# STM32L496RG_Breakout.net
KiCad netlist of a schematic drawn in Altium Designer
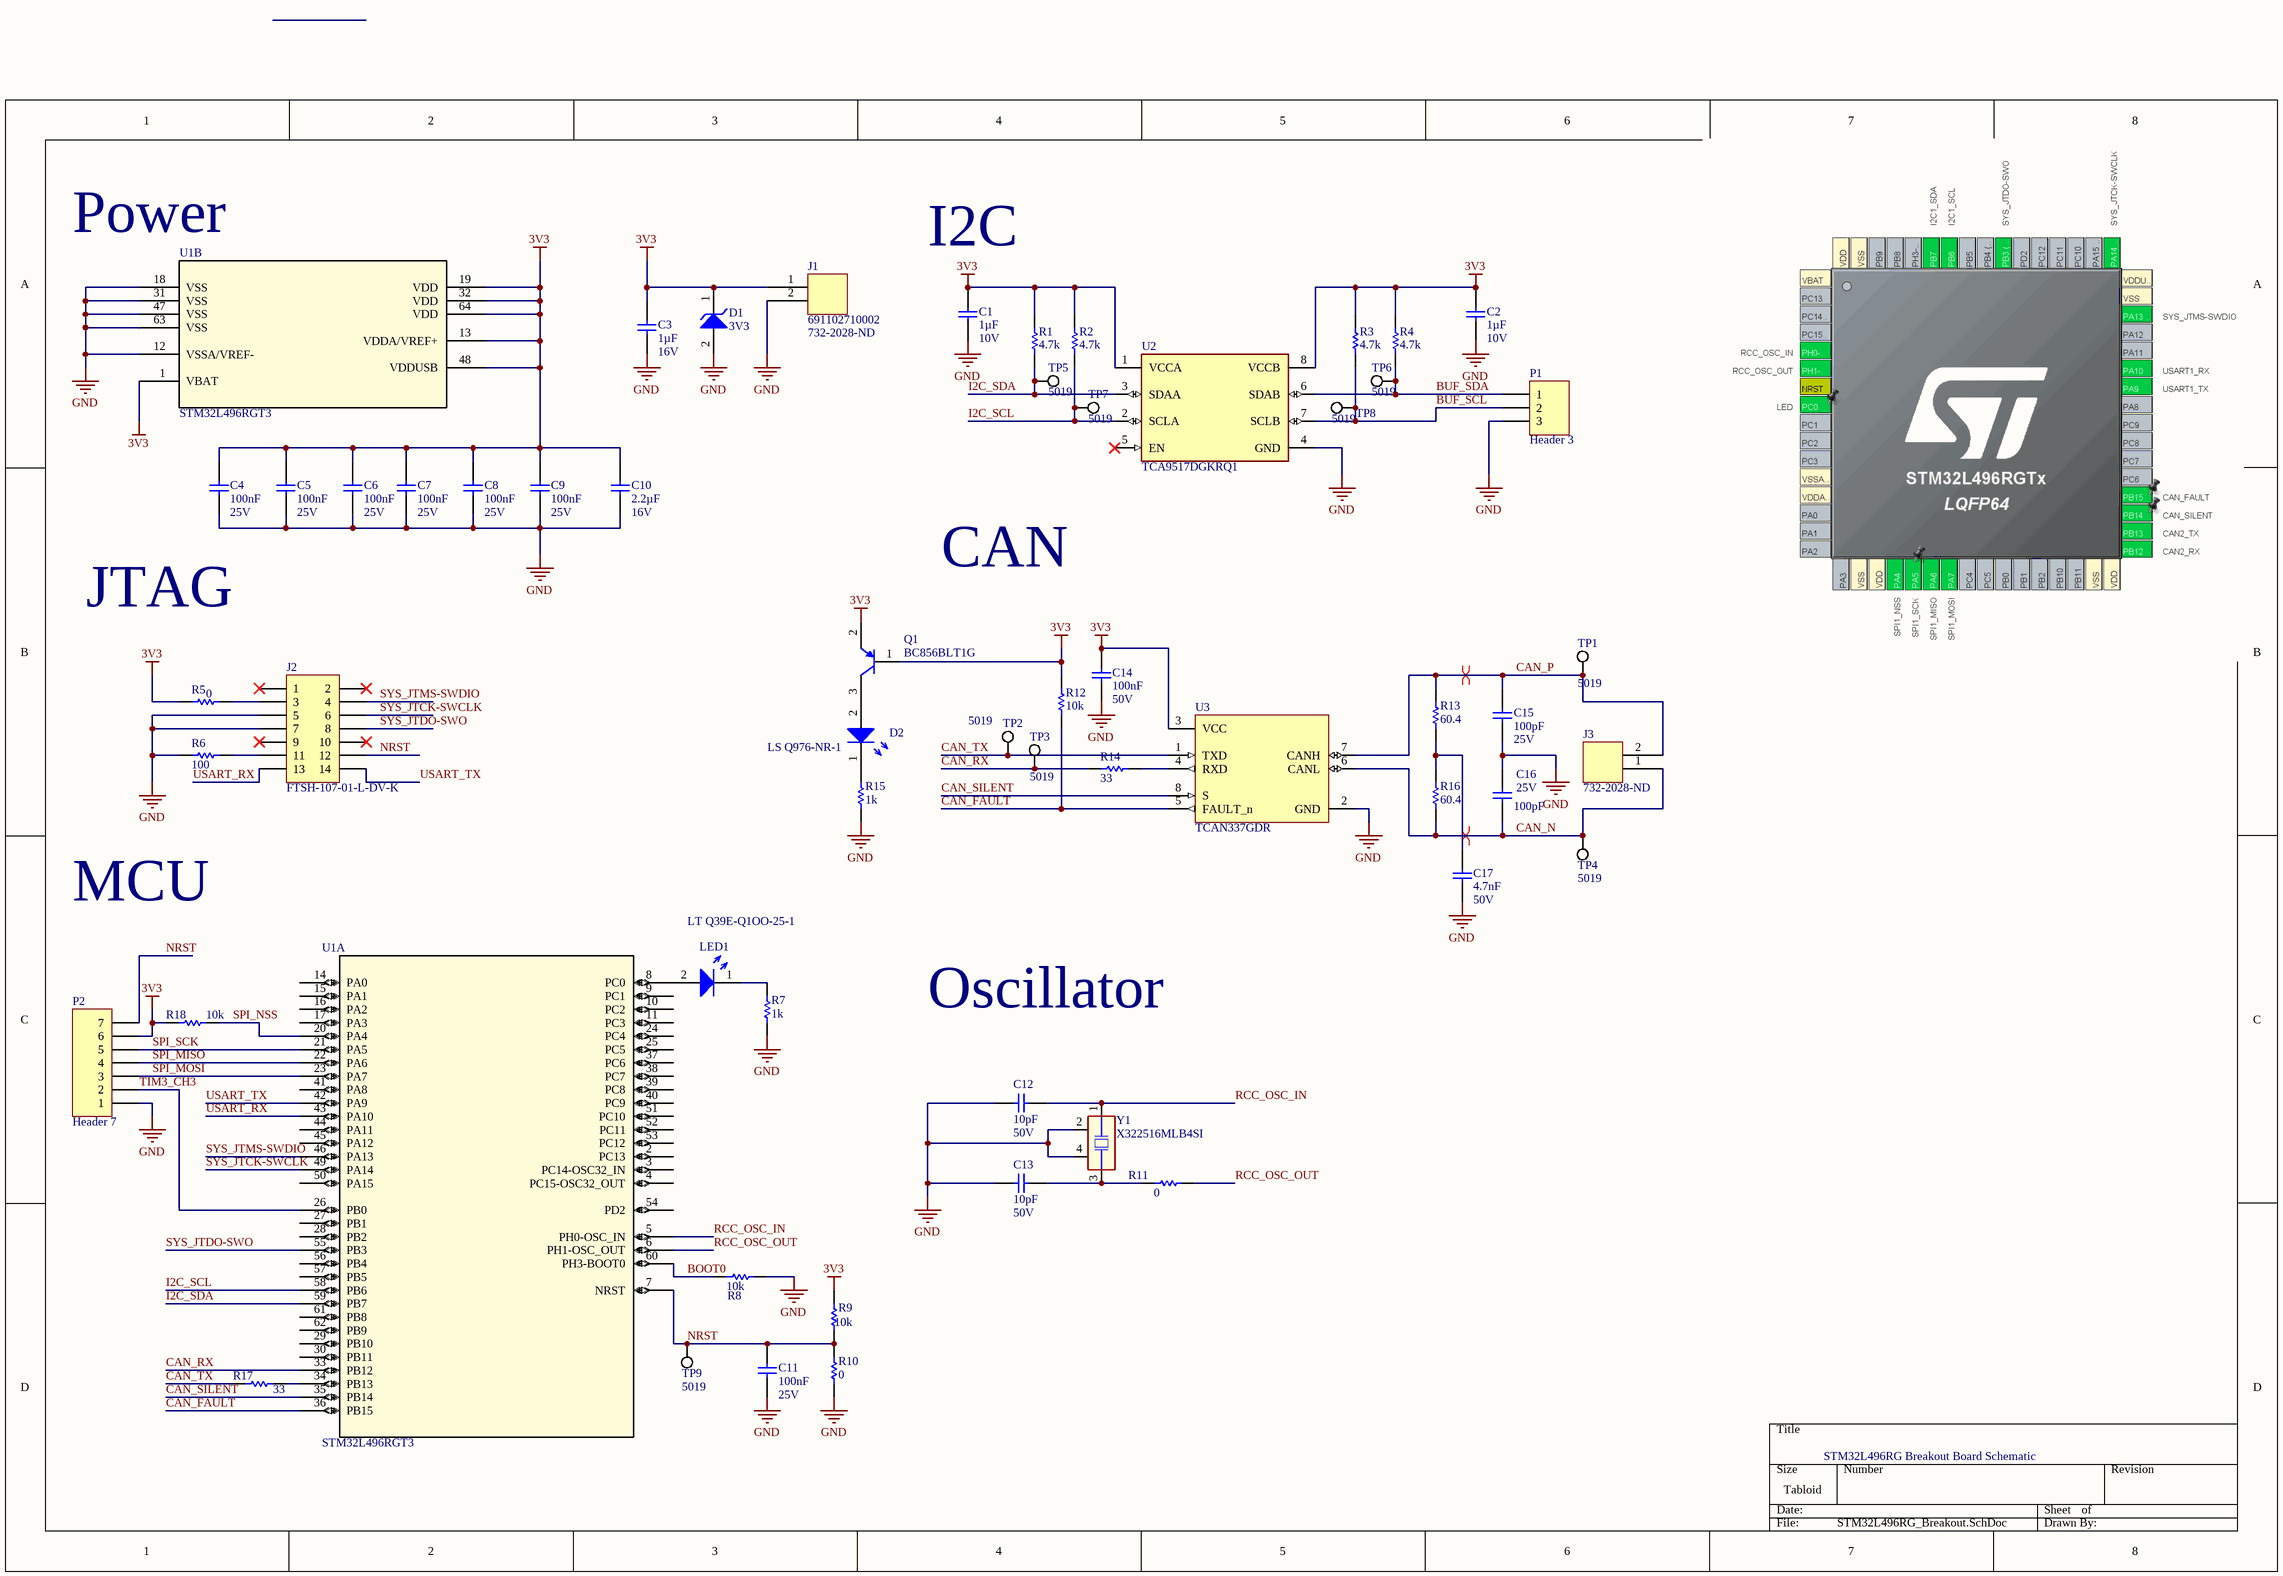
[diagram p0: STM32L496RG_Breakout.SchDoc]

(export (version "E")
  (design (tool "Eeschema 10.0.6"))
  (components
    (comp (ref "C1")
      (value "1µF")
      (footprint "CAP0805R")
      (description "CAP CER 1UF 10V X7R 0805")
      (fields
        (field (name "VOLTAGE RATING") "10V")
        (field (name "MANUFACTURER") "Taiyo Yuden")
        (field (name "TOLERANCE") "10%")
      )
      (libsource (lib "University of Toronto Aerospace Team") (part "Cap-2"))
    )
    (comp (ref "C2")
      (value "1µF")
      (footprint "CAP0805R")
      (description "CAP CER 1UF 10V X7R 0805")
      (fields
        (field (name "VOLTAGE RATING") "10V")
        (field (name "MANUFACTURER") "Taiyo Yuden")
        (field (name "TOLERANCE") "10%")
      )
      (libsource (lib "University of Toronto Aerospace Team") (part "Cap-2"))
    )
    (comp (ref "C3")
      (value "1µF")
      (footprint "CAP0805R")
      (description "CAP CER 1UF 16V X7R 0805")
      (fields
        (field (name "VOLTAGE RATING") "16V")
        (field (name "MANUFACTURER") "Murata Electronics")
        (field (name "TOLERANCE") "10%")
      )
      (libsource (lib "University of Toronto Aerospace Team") (part "Cap-2"))
    )
    (comp (ref "C4")
      (value "100nF")
      (footprint "CAP0603R")
      (description "CAP CER 0.1UF 25V X7R 0603")
      (fields
        (field (name "VOLTAGE RATING") "25V")
        (field (name "TOLERANCE") "10%")
        (field (name "MANUFACTURER") "TDK Corporation")
      )
      (libsource (lib "University of Toronto Aerospace Team") (part "Cap-2"))
    )
    (comp (ref "C5")
      (value "100nF")
      (footprint "CAP0603R")
      (description "CAP CER 0.1UF 25V X7R 0603")
      (fields
        (field (name "VOLTAGE RATING") "25V")
        (field (name "TOLERANCE") "10%")
        (field (name "MANUFACTURER") "TDK Corporation")
      )
      (libsource (lib "University of Toronto Aerospace Team") (part "Cap-2"))
    )
    (comp (ref "C6")
      (value "100nF")
      (footprint "CAP0603R")
      (description "CAP CER 0.1UF 25V X7R 0603")
      (fields
        (field (name "VOLTAGE RATING") "25V")
        (field (name "TOLERANCE") "10%")
        (field (name "MANUFACTURER") "TDK Corporation")
      )
      (libsource (lib "University of Toronto Aerospace Team") (part "Cap-2"))
    )
    (comp (ref "C7")
      (value "100nF")
      (footprint "CAP0603R")
      (description "CAP CER 0.1UF 25V X7R 0603")
      (fields
        (field (name "VOLTAGE RATING") "25V")
        (field (name "TOLERANCE") "10%")
        (field (name "MANUFACTURER") "TDK Corporation")
      )
      (libsource (lib "University of Toronto Aerospace Team") (part "Cap-2"))
    )
    (comp (ref "C8")
      (value "100nF")
      (footprint "CAP0603R")
      (description "CAP CER 0.1UF 25V X7R 0603")
      (fields
        (field (name "VOLTAGE RATING") "25V")
        (field (name "TOLERANCE") "10%")
        (field (name "MANUFACTURER") "TDK Corporation")
      )
      (libsource (lib "University of Toronto Aerospace Team") (part "Cap-2"))
    )
    (comp (ref "C9")
      (value "100nF")
      (footprint "CAP0603R")
      (description "CAP CER 0.1UF 25V X7R 0603")
      (fields
        (field (name "VOLTAGE RATING") "25V")
        (field (name "TOLERANCE") "10%")
        (field (name "MANUFACTURER") "TDK Corporation")
      )
      (libsource (lib "University of Toronto Aerospace Team") (part "Cap-2"))
    )
    (comp (ref "C10")
      (value "2.2µF")
      (footprint "CAP0805R")
      (description "CAP CER 2.2UF 16V X7R 0805")
      (fields
        (field (name "VOLTAGE RATING") "16V")
        (field (name "TOLERANCE") "10%")
        (field (name "MANUFACTURER") "Murata Electronics")
      )
      (libsource (lib "University of Toronto Aerospace Team") (part "Cap-2"))
    )
    (comp (ref "C11")
      (value "100nF")
      (footprint "CAP0603R")
      (description "CAP CER 0.1UF 25V X7R 0603")
      (fields
        (field (name "VOLTAGE RATING") "25V")
        (field (name "TOLERANCE") "10%")
        (field (name "MANUFACTURER") "TDK Corporation")
      )
      (libsource (lib "University of Toronto Aerospace Team") (part "Cap-2"))
    )
    (comp (ref "C12")
      (value "10pF")
      (footprint "CAP0402R")
      (description "CAP CER 10PF 50V C0G/NP0 0402")
      (fields
        (field (name "VOLTAGE RATING") "50V")
        (field (name "TOLERANCE") "5%")
        (field (name "MANUFACTURER") "Murata Electronics")
      )
      (libsource (lib "University of Toronto Aerospace Team") (part "Cap-2"))
    )
    (comp (ref "C13")
      (value "10pF")
      (footprint "CAP0402R")
      (description "CAP CER 10PF 50V C0G/NP0 0402")
      (fields
        (field (name "VOLTAGE RATING") "50V")
        (field (name "TOLERANCE") "5%")
        (field (name "MANUFACTURER") "Murata Electronics")
      )
      (libsource (lib "University of Toronto Aerospace Team") (part "Cap-2"))
    )
    (comp (ref "C14")
      (value "100nF")
      (footprint "CAP0603R")
      (description "CAP CER 0.1UF 50V X7R 0603")
      (fields
        (field (name "VOLTAGE RATING") "50V")
        (field (name "TOLERANCE") "10%")
        (field (name "MANUFACTURER") "TDK Corporation")
      )
      (libsource (lib "University of Toronto Aerospace Team") (part "Cap-2"))
    )
    (comp (ref "C15")
      (value "100pF")
      (footprint "CAP0603R")
      (description "CAP CER 100PF 25V C0G/NP0 0603")
      (fields
        (field (name "VOLTAGE RATING") "25V")
        (field (name "MANUFACTURER") "KEMET")
        (field (name "TOLERANCE") "10%")
      )
      (libsource (lib "University of Toronto Aerospace Team") (part "Cap-2"))
    )
    (comp (ref "C16")
      (value "100pF")
      (footprint "CAP0603R")
      (description "CAP CER 100PF 25V C0G/NP0 0603")
      (fields
        (field (name "VOLTAGE RATING") "25V")
        (field (name "MANUFACTURER") "KEMET")
        (field (name "TOLERANCE") "10%")
      )
      (libsource (lib "University of Toronto Aerospace Team") (part "Cap-2"))
    )
    (comp (ref "C17")
      (value "4.7nF")
      (footprint "CAP0603R")
      (description "CAP CER 4700PF 50V X7R 0603")
      (fields
        (field (name "VOLTAGE RATING") "50V")
        (field (name "TOLERANCE") "10%")
        (field (name "MANUFACTURER") "TDK Corporation")
      )
      (libsource (lib "University of Toronto Aerospace Team") (part "Cap-2"))
    )
    (comp (ref "D1")
      (value "3V3")
      (footprint "ONSC-SOD-323-2-477-02_V")
      (description "Zener Diode, 3.3V V(Z), 6%, 0.3W, Silicon, Unidirectional")
      (libsource (lib "University of Toronto Aerospace Team") (part "ONSC-K1A2-2"))
    )
    (comp (ref "D2")
      (value "LS Q976-NR-1")
      (footprint "LED0603")
      (description "LED RED DIFFUSED 0603 SMD")
      (fields (field (name "MANUFACTURER") "OSRAM Opto Semiconductors Inc."))
      (libsource (lib "University of Toronto Aerospace Team") (part "LED-2"))
    )
    (comp (ref "J1")
      (value "691102710002")
      (footprint "CON2_SCREW_5.00MM_691102710002")
      (description "2 Position Wire to Board Terminal Block Horizontal with Board 0.197\" (5.00mm) Through Hole")
      (fields
        (field (name "SUPPLIER PART NUMBER 1") "732-2028-ND")
        (field (name "MANUFACTURER") "Würth Elektronik")
      )
      (libsource (lib "University of Toronto Aerospace Team") (part "691102710002"))
    )
    (comp (ref "J2")
      (value "FTSH-107-01-L-DV-K")
      (footprint "FP-FTSH-107-01-L-DV-K-MFG")
      (description "Conn Unshrouded Header HDR 14 POS 1.27mm Solder ST Top Entry SMD TIGER CLAW™ Tube")
      (libsource (lib "University of Toronto Aerospace Team") (part "Header 7X2H"))
    )
    (comp (ref "J3")
      (value "691102710002")
      (footprint "CON2_SCREW_5.00MM_691102710002")
      (description "2 Position Wire to Board Terminal Block Horizontal with Board 0.197\" (5.00mm) Through Hole")
      (fields
        (field (name "SUPPLIER PART NUMBER 1") "732-2028-ND")
        (field (name "MANUFACTURER") "Würth Elektronik")
      )
      (libsource (lib "") (part "691102710002_1"))
    )
    (comp (ref "LED1")
      (value "LT Q39E-Q1OO-25-1")
      (footprint "LED0603")
      (description "LED GREEN DIFFUSED 0603 SMD")
      (fields (field (name "MANUFACTURER") "OSRAM Opto Semiconductors Inc."))
      (libsource (lib "University of Toronto Aerospace Team") (part "LED-2"))
    )
    (comp (ref "P1")
      (value "Header 3")
      (footprint "HDR1X3")
      (description "Header, 3-Pin")
      (fields (field (name "PUBLISHER") "Altium Limited"))
      (libsource (lib "University of Toronto Aerospace Team") (part "Header 3H"))
    )
    (comp (ref "P2")
      (value "Header 7")
      (footprint "HDR1X7")
      (description "Header, 7-Pin")
      (fields (field (name "PUBLISHER") "Altium Limited"))
      (libsource (lib "University of Toronto Aerospace Team") (part "Header 7H"))
    )
    (comp (ref "Q1")
      (value "BC856BLT1G")
      (footprint "ONSC-SOT-23-3-318-08_V")
      (description "Small Signal Bipolar Transistor, 0.1A I(C), 65V V(BR)CEO, 1-Element, PNP, Silicon, TO-236AB")
      (libsource (lib "University of Toronto Aerospace Team") (part "ONSC-PNP-B1E2C3-3"))
    )
    (comp (ref "R1")
      (value "4.7k")
      (footprint "RES0603R")
      (description "RES SMD 4.7K OHM 1% 1/10W 0603")
      (fields (field (name "TOLERANCE") "1%") (field (name "POWER") "100mW"))
      (libsource (lib "University of Toronto Aerospace Team") (part "Res-2"))
    )
    (comp (ref "R2")
      (value "4.7k")
      (footprint "RES0603R")
      (description "RES SMD 4.7K OHM 1% 1/10W 0603")
      (fields (field (name "TOLERANCE") "1%") (field (name "POWER") "100mW"))
      (libsource (lib "University of Toronto Aerospace Team") (part "Res-2"))
    )
    (comp (ref "R3")
      (value "4.7k")
      (footprint "RES0603R")
      (description "RES SMD 4.7K OHM 1% 1/10W 0603")
      (fields (field (name "TOLERANCE") "1%") (field (name "POWER") "100mW"))
      (libsource (lib "University of Toronto Aerospace Team") (part "Res-2"))
    )
    (comp (ref "R4")
      (value "4.7k")
      (footprint "RES0603R")
      (description "RES SMD 4.7K OHM 1% 1/10W 0603")
      (fields (field (name "TOLERANCE") "1%") (field (name "POWER") "100mW"))
      (libsource (lib "University of Toronto Aerospace Team") (part "Res-2"))
    )
    (comp (ref "R5")
      (value "0")
      (footprint "RES0805R")
      (description "RES SMD 0 OHM JUMPER 1/8W 0805")
      (fields (field (name "MANUFACTURER") "Panasonic") (field (name "POWER") "125mW"))
      (libsource (lib "University of Toronto Aerospace Team") (part "Res-2"))
    )
    (comp (ref "R6")
      (value "100")
      (footprint "RES0603R")
      (description "RES SMD 100 OHM 5% 1/10W 0603")
      (fields (field (name "POWER") "100mW") (field (name "TOLERANCE") "5%"))
      (libsource (lib "University of Toronto Aerospace Team") (part "Res-2"))
    )
    (comp (ref "R7")
      (value "1k")
      (footprint "RES0805R")
      (description "RES SMD 1K OHM 1% 1/8W 0805")
      (fields (field (name "MANUFACTURER") "Vishay Dale") (field (name "POWER") "125mW"))
      (libsource (lib "University of Toronto Aerospace Team") (part "Res-2"))
    )
    (comp (ref "R8")
      (value "10k")
      (footprint "RES0603R")
      (description "RES SMD 10K OHM 5% 1/10W 0603")
      (fields (field (name "POWER") "100mW") (field (name "TOLERANCE") "5%"))
      (libsource (lib "University of Toronto Aerospace Team") (part "Res-2"))
    )
    (comp (ref "R9")
      (value "10k")
      (footprint "RES0603R")
      (description "RES SMD 10K OHM 5% 1/10W 0603")
      (fields (field (name "POWER") "100mW") (field (name "TOLERANCE") "5%"))
      (libsource (lib "University of Toronto Aerospace Team") (part "Res-2"))
    )
    (comp (ref "R10")
      (value "0")
      (footprint "RES0805R")
      (description "RES SMD 0 OHM JUMPER 1/8W 0805")
      (fields (field (name "MANUFACTURER") "Panasonic") (field (name "POWER") "125mW"))
      (libsource (lib "University of Toronto Aerospace Team") (part "Res-2"))
    )
    (comp (ref "R11")
      (value "0")
      (footprint "RES0805R")
      (description "RES SMD 0 OHM JUMPER 1/8W 0805")
      (fields (field (name "MANUFACTURER") "Panasonic") (field (name "POWER") "125mW"))
      (libsource (lib "University of Toronto Aerospace Team") (part "Res-2"))
    )
    (comp (ref "R12")
      (value "10k")
      (footprint "RES0603R")
      (description "RES SMD 10K OHM 1% 1/10W 0603")
      (fields (field (name "MANUFACTURER") "Vishay Dale") (field (name "POWER") "100mW"))
      (libsource (lib "University of Toronto Aerospace Team") (part "Res-2"))
    )
    (comp (ref "R13")
      (value "60.4")
      (footprint "RES0603R")
      (description "RES SMD 60.4 OHM 1% 1/10W 0603")
      (fields (field (name "TOLERANCE") "1%") (field (name "MANUFACTURER") "Vishay Dale"))
      (libsource (lib "University of Toronto Aerospace Team") (part "Res-2"))
    )
    (comp (ref "R14")
      (value "33")
      (footprint "RES0603R")
      (description "RES SMD 33 OHM 1% 1/10W 0603")
      (fields (field (name "TOLERANCE") "1%") (field (name "POWER") "100mW"))
      (libsource (lib "University of Toronto Aerospace Team") (part "Res-2"))
    )
    (comp (ref "R15")
      (value "1k")
      (footprint "RES0603R")
      (description "RES SMD 1K OHM 1% 1/10W 0603")
      (fields (field (name "POWER") "100mW") (field (name "MANUFACTURER") "Vishay Dale"))
      (libsource (lib "University of Toronto Aerospace Team") (part "Res-2"))
    )
    (comp (ref "R16")
      (value "60.4")
      (footprint "RES0603R")
      (description "RES SMD 60.4 OHM 1% 1/10W 0603")
      (fields (field (name "TOLERANCE") "1%") (field (name "MANUFACTURER") "Vishay Dale"))
      (libsource (lib "University of Toronto Aerospace Team") (part "Res-2"))
    )
    (comp (ref "R17")
      (value "33")
      (footprint "RES0603R")
      (description "RES SMD 33 OHM 1% 1/10W 0603")
      (fields (field (name "TOLERANCE") "1%") (field (name "POWER") "100mW"))
      (libsource (lib "University of Toronto Aerospace Team") (part "Res-2"))
    )
    (comp (ref "R18")
      (value "10k")
      (footprint "RES0603R")
      (description "RES SMD 10K OHM 1% 1/10W 0603")
      (fields (field (name "TOLERANCE") "1%") (field (name "POWER") "100mW"))
      (libsource (lib "University of Toronto Aerospace Team") (part "Res-2"))
    )
    (comp (ref "TP1")
      (value "5019")
      (footprint "KSTN-5019_V")
      (description "Interconnection Device")
      (libsource (lib "University of Toronto Aerospace Team") (part "TESTPOINT_WHITE"))
    )
    (comp (ref "TP2")
      (value "5019")
      (footprint "KSTN-5019_V")
      (description "Interconnection Device")
      (libsource (lib "University of Toronto Aerospace Team") (part "TESTPOINT_WHITE"))
    )
    (comp (ref "TP3")
      (value "5019")
      (footprint "KSTN-5019_V")
      (description "Interconnection Device")
      (libsource (lib "University of Toronto Aerospace Team") (part "TESTPOINT_WHITE"))
    )
    (comp (ref "TP4")
      (value "5019")
      (footprint "KSTN-5019_V")
      (description "Interconnection Device")
      (libsource (lib "University of Toronto Aerospace Team") (part "TESTPOINT_WHITE"))
    )
    (comp (ref "TP5")
      (value "5019")
      (footprint "KSTN-5019_V")
      (description "Interconnection Device")
      (libsource (lib "University of Toronto Aerospace Team") (part "TESTPOINT_WHITE"))
    )
    (comp (ref "TP6")
      (value "5019")
      (footprint "KSTN-5019_V")
      (description "Interconnection Device")
      (libsource (lib "University of Toronto Aerospace Team") (part "TESTPOINT_WHITE"))
    )
    (comp (ref "TP7")
      (value "5019")
      (footprint "KSTN-5019_V")
      (description "Interconnection Device")
      (libsource (lib "University of Toronto Aerospace Team") (part "TESTPOINT_WHITE"))
    )
    (comp (ref "TP8")
      (value "5019")
      (footprint "KSTN-5019_V")
      (description "Interconnection Device")
      (libsource (lib "University of Toronto Aerospace Team") (part "TESTPOINT_WHITE"))
    )
    (comp (ref "TP9")
      (value "5019")
      (footprint "KSTN-5019_V")
      (description "Interconnection Device")
      (libsource (lib "University of Toronto Aerospace Team") (part "TESTPOINT_WHITE"))
    )
    (comp (ref "U1")
      (value "STM32L496RGT3")
      (footprint "LQFP64-10x10mm")
      (fields (field (name "COPYRIGHT") "Copyright (C) 2025 Ultra Librarian. All rights reserved."))
      (libsource (lib "STM32L496RGT3") (part "STM32L496RGT3"))
    )
    (comp (ref "U2")
      (value "TCA9517DGKRQ1")
      (footprint "FP-DGK0008A-MFG")
      (description "Voltage Level Translator Bidirectional 1 Circuit 2 Channel 8-VSSOP")
      (libsource (lib "University of Toronto Aerospace Team") (part "TCA9517DGKRQ1"))
    )
    (comp (ref "U3")
      (value "TCAN337GDR")
      (footprint "TI-D0008A")
      (description "Interface Circuit, PDSO8")
      (fields (field (name "MANUFACTURER") "Texas Instruments"))
      (libsource (lib "University of Toronto Aerospace Team") (part "TCAN337"))
    )
    (comp (ref "Y1")
      (value "X322516MLB4SI")
      (footprint "X322516MLB4SI-Footprint-1")
      (description "16MHz Surface Mount Crystal 9pF ±10ppm ±20ppm SMD3225-4P Crystals ROHS")
      (libsource (lib "University of Toronto Aerospace Team") (part "CRYSTAL-2"))
    )
  )
  (nets
    (net (code "1") (name "/BOOT0") (class "Default")
      (node (ref "R8") (pin "1") (pinfunction "1_1") (pintype "passive"))
      (node (ref "U1") (pin "60") (pinfunction "PH3-BOOT0_60") (pintype "bidirectional"))
    )
    (net (code "2") (name "/BUF_SCL") (class "Default")
      (node (ref "P1") (pin "2") (pinfunction "2_2") (pintype "passive"))
      (node (ref "R3") (pin "1") (pinfunction "1_1") (pintype "passive"))
      (node (ref "TP8") (pin "1") (pinfunction "1_1") (pintype "passive"))
      (node (ref "U2") (pin "7") (pinfunction "SCLB_7") (pintype "bidirectional"))
    )
    (net (code "3") (name "/BUF_SDA") (class "Default")
      (node (ref "P1") (pin "1") (pinfunction "1_1") (pintype "passive"))
      (node (ref "R4") (pin "1") (pinfunction "1_1") (pintype "passive"))
      (node (ref "TP6") (pin "1") (pinfunction "1_1") (pintype "passive"))
      (node (ref "U2") (pin "6") (pinfunction "SDAB_6") (pintype "bidirectional"))
    )
    (net (code "4") (name "/CAN_FAULT") (class "Default")
      (node (ref "R12") (pin "1") (pinfunction "1_1") (pintype "passive"))
      (node (ref "U1") (pin "36") (pinfunction "PB15_36") (pintype "bidirectional"))
      (node (ref "U3") (pin "5") (pinfunction "FAULT_n_5") (pintype "output"))
    )
    (net (code "5") (name "/CAN_N") (class "Default")
      (node (ref "C16") (pin "1") (pinfunction "1_1") (pintype "passive"))
      (node (ref "J3") (pin "1") (pinfunction "1_1") (pintype "passive"))
      (node (ref "R16") (pin "1") (pinfunction "1_1") (pintype "passive"))
      (node (ref "TP4") (pin "1") (pinfunction "1_1") (pintype "passive"))
      (node (ref "U3") (pin "6") (pinfunction "CANL_6") (pintype "bidirectional"))
    )
    (net (code "6") (name "/CAN_P") (class "Default")
      (node (ref "C15") (pin "2") (pinfunction "2_2") (pintype "passive"))
      (node (ref "J3") (pin "2") (pinfunction "2_2") (pintype "passive"))
      (node (ref "R13") (pin "2") (pinfunction "2_2") (pintype "passive"))
      (node (ref "TP1") (pin "1") (pinfunction "1_1") (pintype "passive"))
      (node (ref "U3") (pin "7") (pinfunction "CANH_7") (pintype "bidirectional"))
    )
    (net (code "7") (name "/CAN_RX") (class "Default")
      (node (ref "R14") (pin "1") (pinfunction "1_1") (pintype "passive"))
      (node (ref "TP3") (pin "1") (pinfunction "1_1") (pintype "passive"))
      (node (ref "U1") (pin "33") (pinfunction "PB12_33") (pintype "bidirectional"))
    )
    (net (code "8") (name "/CAN_SILENT") (class "Default")
      (node (ref "U1") (pin "35") (pinfunction "PB14_35") (pintype "bidirectional"))
      (node (ref "U3") (pin "8") (pinfunction "S_8") (pintype "input"))
    )
    (net (code "9") (name "/CAN_TX") (class "Default")
      (node (ref "R17") (pin "1") (pinfunction "1_1") (pintype "passive"))
      (node (ref "TP2") (pin "1") (pinfunction "1_1") (pintype "passive"))
      (node (ref "U3") (pin "1") (pinfunction "TXD_1") (pintype "input"))
    )
    (net (code "10") (name "/I2C_SCL") (class "Default")
      (node (ref "R2") (pin "1") (pinfunction "1_1") (pintype "passive"))
      (node (ref "TP7") (pin "1") (pinfunction "1_1") (pintype "passive"))
      (node (ref "U1") (pin "58") (pinfunction "PB6_58") (pintype "bidirectional"))
      (node (ref "U2") (pin "2") (pinfunction "SCLA_2") (pintype "bidirectional"))
    )
    (net (code "11") (name "/I2C_SDA") (class "Default")
      (node (ref "R1") (pin "1") (pinfunction "1_1") (pintype "passive"))
      (node (ref "TP5") (pin "1") (pinfunction "1_1") (pintype "passive"))
      (node (ref "U1") (pin "59") (pinfunction "PB7_59") (pintype "bidirectional"))
      (node (ref "U2") (pin "3") (pinfunction "SDAA_3") (pintype "bidirectional"))
    )
    (net (code "12") (name "/NRST") (class "Default")
      (node (ref "C11") (pin "2") (pinfunction "2_2") (pintype "passive"))
      (node (ref "J2") (pin "12") (pinfunction "12_12") (pintype "passive"))
      (node (ref "P2") (pin "7") (pinfunction "7_7") (pintype "passive"))
      (node (ref "R10") (pin "2") (pinfunction "2_2") (pintype "passive"))
      (node (ref "R9") (pin "1") (pinfunction "1_1") (pintype "passive"))
      (node (ref "TP9") (pin "1") (pinfunction "1_1") (pintype "passive"))
      (node (ref "U1") (pin "7") (pinfunction "NRST_7") (pintype "bidirectional"))
    )
    (net (code "13") (name "/RCC_OSC_IN") (class "Default")
      (node (ref "C12") (pin "1") (pinfunction "1_1") (pintype "passive"))
      (node (ref "U1") (pin "5") (pinfunction "PH0-OSC_IN_5") (pintype "bidirectional"))
      (node (ref "Y1") (pin "1") (pinfunction "OSC1_1") (pintype "passive"))
    )
    (net (code "14") (name "/RCC_OSC_OUT") (class "Default")
      (node (ref "R11") (pin "2") (pinfunction "2_2") (pintype "passive"))
      (node (ref "U1") (pin "6") (pinfunction "PH1-OSC_OUT_6") (pintype "bidirectional"))
    )
    (net (code "15") (name "/SPI_MISO") (class "Default")
      (node (ref "P2") (pin "4") (pinfunction "4_4") (pintype "passive"))
      (node (ref "U1") (pin "22") (pinfunction "PA6_22") (pintype "bidirectional"))
    )
    (net (code "16") (name "/SPI_MOSI") (class "Default")
      (node (ref "P2") (pin "3") (pinfunction "3_3") (pintype "passive"))
      (node (ref "U1") (pin "23") (pinfunction "PA7_23") (pintype "bidirectional"))
    )
    (net (code "17") (name "/SPI_NSS") (class "Default")
      (node (ref "R18") (pin "2") (pinfunction "2_2") (pintype "passive"))
      (node (ref "U1") (pin "20") (pinfunction "PA4_20") (pintype "bidirectional"))
    )
    (net (code "18") (name "/SPI_SCK") (class "Default")
      (node (ref "P2") (pin "5") (pinfunction "5_5") (pintype "passive"))
      (node (ref "U1") (pin "21") (pinfunction "PA5_21") (pintype "bidirectional"))
    )
    (net (code "19") (name "/SYS_JTCK-SWCLK") (class "Default")
      (node (ref "J2") (pin "6") (pinfunction "6_6") (pintype "passive"))
      (node (ref "U1") (pin "49") (pinfunction "PA14_49") (pintype "bidirectional"))
    )
    (net (code "20") (name "/SYS_JTDO-SWO") (class "Default")
      (node (ref "J2") (pin "8") (pinfunction "8_8") (pintype "passive"))
      (node (ref "U1") (pin "55") (pinfunction "PB3_55") (pintype "bidirectional"))
    )
    (net (code "21") (name "/SYS_JTMS-SWDIO") (class "Default")
      (node (ref "J2") (pin "4") (pinfunction "4_4") (pintype "passive"))
      (node (ref "U1") (pin "46") (pinfunction "PA13_46") (pintype "bidirectional"))
    )
    (net (code "22") (name "/TIM3_CH3") (class "Default")
      (node (ref "P2") (pin "2") (pinfunction "2_2") (pintype "passive"))
      (node (ref "U1") (pin "26") (pinfunction "PB0_26") (pintype "bidirectional"))
    )
    (net (code "23") (name "/USART_RX") (class "Default")
      (node (ref "J2") (pin "13") (pinfunction "13_13") (pintype "passive"))
      (node (ref "U1") (pin "43") (pinfunction "PA10_43") (pintype "bidirectional"))
    )
    (net (code "24") (name "/USART_TX") (class "Default")
      (node (ref "J2") (pin "14") (pinfunction "14_14") (pintype "passive"))
      (node (ref "U1") (pin "42") (pinfunction "PA9_42") (pintype "bidirectional"))
    )
    (net (code "25") (name "3V3") (class "Default")
      (node (ref "C1") (pin "2") (pinfunction "2_2") (pintype "passive"))
      (node (ref "C10") (pin "2") (pinfunction "2_2") (pintype "passive"))
      (node (ref "C14") (pin "2") (pinfunction "2_2") (pintype "passive"))
      (node (ref "C2") (pin "2") (pinfunction "2_2") (pintype "passive"))
      (node (ref "C3") (pin "2") (pinfunction "2_2") (pintype "passive"))
      (node (ref "C4") (pin "2") (pinfunction "2_2") (pintype "passive"))
      (node (ref "C5") (pin "2") (pinfunction "2_2") (pintype "passive"))
      (node (ref "C6") (pin "2") (pinfunction "2_2") (pintype "passive"))
      (node (ref "C7") (pin "2") (pinfunction "2_2") (pintype "passive"))
      (node (ref "C8") (pin "2") (pinfunction "2_2") (pintype "passive"))
      (node (ref "C9") (pin "2") (pinfunction "2_2") (pintype "passive"))
      (node (ref "D1") (pin "1") (pinfunction "K_1") (pintype "passive"))
      (node (ref "J1") (pin "1") (pinfunction "1_1") (pintype "passive"))
      (node (ref "P2") (pin "6") (pinfunction "6_6") (pintype "passive"))
      (node (ref "Q1") (pin "1") (pinfunction "B_1") (pintype "passive"))
      (node (ref "Q1") (pin "2") (pinfunction "E_2") (pintype "passive"))
      (node (ref "R1") (pin "2") (pinfunction "2_2") (pintype "passive"))
      (node (ref "R12") (pin "2") (pinfunction "2_2") (pintype "passive"))
      (node (ref "R18") (pin "1") (pinfunction "1_1") (pintype "passive"))
      (node (ref "R2") (pin "2") (pinfunction "2_2") (pintype "passive"))
      (node (ref "R3") (pin "2") (pinfunction "2_2") (pintype "passive"))
      (node (ref "R4") (pin "2") (pinfunction "2_2") (pintype "passive"))
      (node (ref "R5") (pin "1") (pinfunction "1_1") (pintype "passive"))
      (node (ref "R9") (pin "2") (pinfunction "2_2") (pintype "passive"))
      (node (ref "U1") (pin "1") (pinfunction "VBAT_1") (pintype "power_in"))
      (node (ref "U1") (pin "13") (pinfunction "VDDA/VREF+_13") (pintype "power_in"))
      (node (ref "U1") (pin "19") (pinfunction "VDD_19") (pintype "power_in"))
      (node (ref "U1") (pin "32") (pinfunction "VDD_32") (pintype "power_in"))
      (node (ref "U1") (pin "48") (pinfunction "VDDUSB_48") (pintype "power_in"))
      (node (ref "U1") (pin "64") (pinfunction "VDD_64") (pintype "power_in"))
      (node (ref "U2") (pin "1") (pinfunction "VCCA_1") (pintype "power_in"))
      (node (ref "U2") (pin "8") (pinfunction "VCCB_8") (pintype "power_in"))
      (node (ref "U3") (pin "3") (pinfunction "VCC_3") (pintype "power_in"))
    )
    (net (code "26") (name "GND") (class "Default")
      (node (ref "C1") (pin "1") (pinfunction "1_1") (pintype "passive"))
      (node (ref "C10") (pin "1") (pinfunction "1_1") (pintype "passive"))
      (node (ref "C11") (pin "1") (pinfunction "1_1") (pintype "passive"))
      (node (ref "C12") (pin "2") (pinfunction "2_2") (pintype "passive"))
      (node (ref "C13") (pin "2") (pinfunction "2_2") (pintype "passive"))
      (node (ref "C14") (pin "1") (pinfunction "1_1") (pintype "passive"))
      (node (ref "C15") (pin "1") (pinfunction "1_1") (pintype "passive"))
      (node (ref "C16") (pin "2") (pinfunction "2_2") (pintype "passive"))
      (node (ref "C17") (pin "1") (pinfunction "1_1") (pintype "passive"))
      (node (ref "C2") (pin "1") (pinfunction "1_1") (pintype "passive"))
      (node (ref "C3") (pin "1") (pinfunction "1_1") (pintype "passive"))
      (node (ref "C4") (pin "1") (pinfunction "1_1") (pintype "passive"))
      (node (ref "C5") (pin "1") (pinfunction "1_1") (pintype "passive"))
      (node (ref "C6") (pin "1") (pinfunction "1_1") (pintype "passive"))
      (node (ref "C7") (pin "1") (pinfunction "1_1") (pintype "passive"))
      (node (ref "C8") (pin "1") (pinfunction "1_1") (pintype "passive"))
      (node (ref "C9") (pin "1") (pinfunction "1_1") (pintype "passive"))
      (node (ref "D1") (pin "2") (pinfunction "A_2") (pintype "passive"))
      (node (ref "J1") (pin "2") (pinfunction "2_2") (pintype "passive"))
      (node (ref "J2") (pin "5") (pinfunction "5_5") (pintype "passive"))
      (node (ref "J2") (pin "7") (pinfunction "7_7") (pintype "passive"))
      (node (ref "P1") (pin "3") (pinfunction "3_3") (pintype "passive"))
      (node (ref "P2") (pin "1") (pinfunction "1_1") (pintype "passive"))
      (node (ref "R10") (pin "1") (pinfunction "1_1") (pintype "passive"))
      (node (ref "R15") (pin "1") (pinfunction "1_1") (pintype "passive"))
      (node (ref "R6") (pin "1") (pinfunction "1_1") (pintype "passive"))
      (node (ref "R7") (pin "1") (pinfunction "1_1") (pintype "passive"))
      (node (ref "R8") (pin "2") (pinfunction "2_2") (pintype "passive"))
      (node (ref "U1") (pin "12") (pinfunction "VSSA/VREF-_12") (pintype "power_in"))
      (node (ref "U1") (pin "18") (pinfunction "VSS_18") (pintype "power_in"))
      (node (ref "U1") (pin "31") (pinfunction "VSS_31") (pintype "power_in"))
      (node (ref "U1") (pin "47") (pinfunction "VSS_47") (pintype "power_in"))
      (node (ref "U1") (pin "63") (pinfunction "VSS_63") (pintype "power_in"))
      (node (ref "U2") (pin "4") (pinfunction "GND_4") (pintype "power_in"))
      (node (ref "U3") (pin "2") (pinfunction "GND_2") (pintype "power_in"))
      (node (ref "Y1") (pin "2") (pinfunction "GND_2") (pintype "passive"))
      (node (ref "Y1") (pin "4") (pinfunction "GND_4") (pintype "passive"))
    )
    (net (code "27") (name "Net-(C17-Pad2)") (class "Default")
      (node (ref "C17") (pin "2") (pinfunction "2_2") (pintype "passive"))
      (node (ref "R13") (pin "1") (pinfunction "1_1") (pintype "passive"))
      (node (ref "R16") (pin "2") (pinfunction "2_2") (pintype "passive"))
    )
    (net (code "28") (name "Net-(D2-Anode)") (class "Default")
      (node (ref "D2") (pin "2") (pinfunction "Anode_2") (pintype "passive"))
      (node (ref "Q1") (pin "3") (pinfunction "C_3") (pintype "passive"))
    )
    (net (code "29") (name "Net-(D2-Cathode)") (class "Default")
      (node (ref "D2") (pin "1") (pinfunction "Cathode_1") (pintype "passive"))
      (node (ref "R15") (pin "2") (pinfunction "2_2") (pintype "passive"))
    )
    (net (code "30") (name "Net-(J2-Pad3)") (class "Default")
      (node (ref "J2") (pin "3") (pinfunction "3_3") (pintype "passive"))
      (node (ref "R5") (pin "2") (pinfunction "2_2") (pintype "passive"))
    )
    (net (code "31") (name "Net-(J2-Pad11)") (class "Default")
      (node (ref "J2") (pin "11") (pinfunction "11_11") (pintype "passive"))
      (node (ref "R6") (pin "2") (pinfunction "2_2") (pintype "passive"))
    )
    (net (code "32") (name "Net-(LED1-Anode)") (class "Default")
      (node (ref "LED1") (pin "2") (pinfunction "Anode_2") (pintype "passive"))
      (node (ref "U1") (pin "8") (pinfunction "PC0_8") (pintype "bidirectional"))
    )
    (net (code "33") (name "Net-(LED1-Cathode)") (class "Default")
      (node (ref "LED1") (pin "1") (pinfunction "Cathode_1") (pintype "passive"))
      (node (ref "R7") (pin "2") (pinfunction "2_2") (pintype "passive"))
    )
    (net (code "34") (name "Net-(U1A-PB13)") (class "Default")
      (node (ref "R17") (pin "2") (pinfunction "2_2") (pintype "passive"))
      (node (ref "U1") (pin "34") (pinfunction "PB13_34") (pintype "bidirectional"))
    )
    (net (code "35") (name "Net-(U3-RXD)") (class "Default")
      (node (ref "R14") (pin "2") (pinfunction "2_2") (pintype "passive"))
      (node (ref "U3") (pin "4") (pinfunction "RXD_4") (pintype "output"))
    )
    (net (code "36") (name "Net-(Y1-OSC2)") (class "Default")
      (node (ref "C13") (pin "1") (pinfunction "1_1") (pintype "passive"))
      (node (ref "R11") (pin "1") (pinfunction "1_1") (pintype "passive"))
      (node (ref "Y1") (pin "3") (pinfunction "OSC2_3") (pintype "passive"))
    )
    (net (code "37") (name "unconnected-(J2-Pad1)") (class "Default")
      (node (ref "J2") (pin "1") (pinfunction "1_1") (pintype "passive+no_connect"))
    )
    (net (code "38") (name "unconnected-(J2-Pad2)") (class "Default")
      (node (ref "J2") (pin "2") (pinfunction "2_2") (pintype "passive+no_connect"))
    )
    (net (code "39") (name "unconnected-(J2-Pad9)") (class "Default")
      (node (ref "J2") (pin "9") (pinfunction "9_9") (pintype "passive+no_connect"))
    )
    (net (code "40") (name "unconnected-(J2-Pad10)") (class "Default")
      (node (ref "J2") (pin "10") (pinfunction "10_10") (pintype "passive+no_connect"))
    )
    (net (code "41") (name "unconnected-(U1A-PA0-Pad14)") (class "Default")
      (node (ref "U1") (pin "14") (pinfunction "PA0_14") (pintype "bidirectional"))
    )
    (net (code "42") (name "unconnected-(U1A-PA1-Pad15)") (class "Default")
      (node (ref "U1") (pin "15") (pinfunction "PA1_15") (pintype "bidirectional"))
    )
    (net (code "43") (name "unconnected-(U1A-PA2-Pad16)") (class "Default")
      (node (ref "U1") (pin "16") (pinfunction "PA2_16") (pintype "bidirectional"))
    )
    (net (code "44") (name "unconnected-(U1A-PA3-Pad17)") (class "Default")
      (node (ref "U1") (pin "17") (pinfunction "PA3_17") (pintype "bidirectional"))
    )
    (net (code "45") (name "unconnected-(U1A-PA8-Pad41)") (class "Default")
      (node (ref "U1") (pin "41") (pinfunction "PA8_41") (pintype "bidirectional"))
    )
    (net (code "46") (name "unconnected-(U1A-PA11-Pad44)") (class "Default")
      (node (ref "U1") (pin "44") (pinfunction "PA11_44") (pintype "bidirectional"))
    )
    (net (code "47") (name "unconnected-(U1A-PA12-Pad45)") (class "Default")
      (node (ref "U1") (pin "45") (pinfunction "PA12_45") (pintype "bidirectional"))
    )
    (net (code "48") (name "unconnected-(U1A-PA15-Pad50)") (class "Default")
      (node (ref "U1") (pin "50") (pinfunction "PA15_50") (pintype "bidirectional"))
    )
    (net (code "49") (name "unconnected-(U1A-PB1-Pad27)") (class "Default")
      (node (ref "U1") (pin "27") (pinfunction "PB1_27") (pintype "bidirectional"))
    )
    (net (code "50") (name "unconnected-(U1A-PB2-Pad28)") (class "Default")
      (node (ref "U1") (pin "28") (pinfunction "PB2_28") (pintype "bidirectional"))
    )
    (net (code "51") (name "unconnected-(U1A-PB4-Pad56)") (class "Default")
      (node (ref "U1") (pin "56") (pinfunction "PB4_56") (pintype "bidirectional"))
    )
    (net (code "52") (name "unconnected-(U1A-PB5-Pad57)") (class "Default")
      (node (ref "U1") (pin "57") (pinfunction "PB5_57") (pintype "bidirectional"))
    )
    (net (code "53") (name "unconnected-(U1A-PB8-Pad61)") (class "Default")
      (node (ref "U1") (pin "61") (pinfunction "PB8_61") (pintype "bidirectional"))
    )
    (net (code "54") (name "unconnected-(U1A-PB9-Pad62)") (class "Default")
      (node (ref "U1") (pin "62") (pinfunction "PB9_62") (pintype "bidirectional"))
    )
    (net (code "55") (name "unconnected-(U1A-PB10-Pad29)") (class "Default")
      (node (ref "U1") (pin "29") (pinfunction "PB10_29") (pintype "bidirectional"))
    )
    (net (code "56") (name "unconnected-(U1A-PB11-Pad30)") (class "Default")
      (node (ref "U1") (pin "30") (pinfunction "PB11_30") (pintype "bidirectional"))
    )
    (net (code "57") (name "unconnected-(U1A-PC1-Pad9)") (class "Default")
      (node (ref "U1") (pin "9") (pinfunction "PC1_9") (pintype "bidirectional"))
    )
    (net (code "58") (name "unconnected-(U1A-PC2-Pad10)") (class "Default")
      (node (ref "U1") (pin "10") (pinfunction "PC2_10") (pintype "bidirectional"))
    )
    (net (code "59") (name "unconnected-(U1A-PC3-Pad11)") (class "Default")
      (node (ref "U1") (pin "11") (pinfunction "PC3_11") (pintype "bidirectional"))
    )
    (net (code "60") (name "unconnected-(U1A-PC4-Pad24)") (class "Default")
      (node (ref "U1") (pin "24") (pinfunction "PC4_24") (pintype "bidirectional"))
    )
    (net (code "61") (name "unconnected-(U1A-PC5-Pad25)") (class "Default")
      (node (ref "U1") (pin "25") (pinfunction "PC5_25") (pintype "bidirectional"))
    )
    (net (code "62") (name "unconnected-(U1A-PC6-Pad37)") (class "Default")
      (node (ref "U1") (pin "37") (pinfunction "PC6_37") (pintype "bidirectional"))
    )
    (net (code "63") (name "unconnected-(U1A-PC7-Pad38)") (class "Default")
      (node (ref "U1") (pin "38") (pinfunction "PC7_38") (pintype "bidirectional"))
    )
    (net (code "64") (name "unconnected-(U1A-PC8-Pad39)") (class "Default")
      (node (ref "U1") (pin "39") (pinfunction "PC8_39") (pintype "bidirectional"))
    )
    (net (code "65") (name "unconnected-(U1A-PC9-Pad40)") (class "Default")
      (node (ref "U1") (pin "40") (pinfunction "PC9_40") (pintype "bidirectional"))
    )
    (net (code "66") (name "unconnected-(U1A-PC10-Pad51)") (class "Default")
      (node (ref "U1") (pin "51") (pinfunction "PC10_51") (pintype "bidirectional"))
    )
    (net (code "67") (name "unconnected-(U1A-PC11-Pad52)") (class "Default")
      (node (ref "U1") (pin "52") (pinfunction "PC11_52") (pintype "bidirectional"))
    )
    (net (code "68") (name "unconnected-(U1A-PC12-Pad53)") (class "Default")
      (node (ref "U1") (pin "53") (pinfunction "PC12_53") (pintype "bidirectional"))
    )
    (net (code "69") (name "unconnected-(U1A-PC13-Pad2)") (class "Default")
      (node (ref "U1") (pin "2") (pinfunction "PC13_2") (pintype "bidirectional"))
    )
    (net (code "70") (name "unconnected-(U1A-PC14-OSC32_IN-Pad3)") (class "Default")
      (node (ref "U1") (pin "3") (pinfunction "PC14-OSC32_IN_3") (pintype "bidirectional"))
    )
    (net (code "71") (name "unconnected-(U1A-PC15-OSC32_OUT-Pad4)") (class "Default")
      (node (ref "U1") (pin "4") (pinfunction "PC15-OSC32_OUT_4") (pintype "bidirectional"))
    )
    (net (code "72") (name "unconnected-(U1A-PD2-Pad54)") (class "Default")
      (node (ref "U1") (pin "54") (pinfunction "PD2_54") (pintype "bidirectional"))
    )
    (net (code "73") (name "unconnected-(U2-EN-Pad5)") (class "Default")
      (node (ref "U2") (pin "5") (pinfunction "EN_5") (pintype "input+no_connect"))
    )
  )
)
